# gain_mute.net
KiCad netlist of a schematic drawn in EAGLE
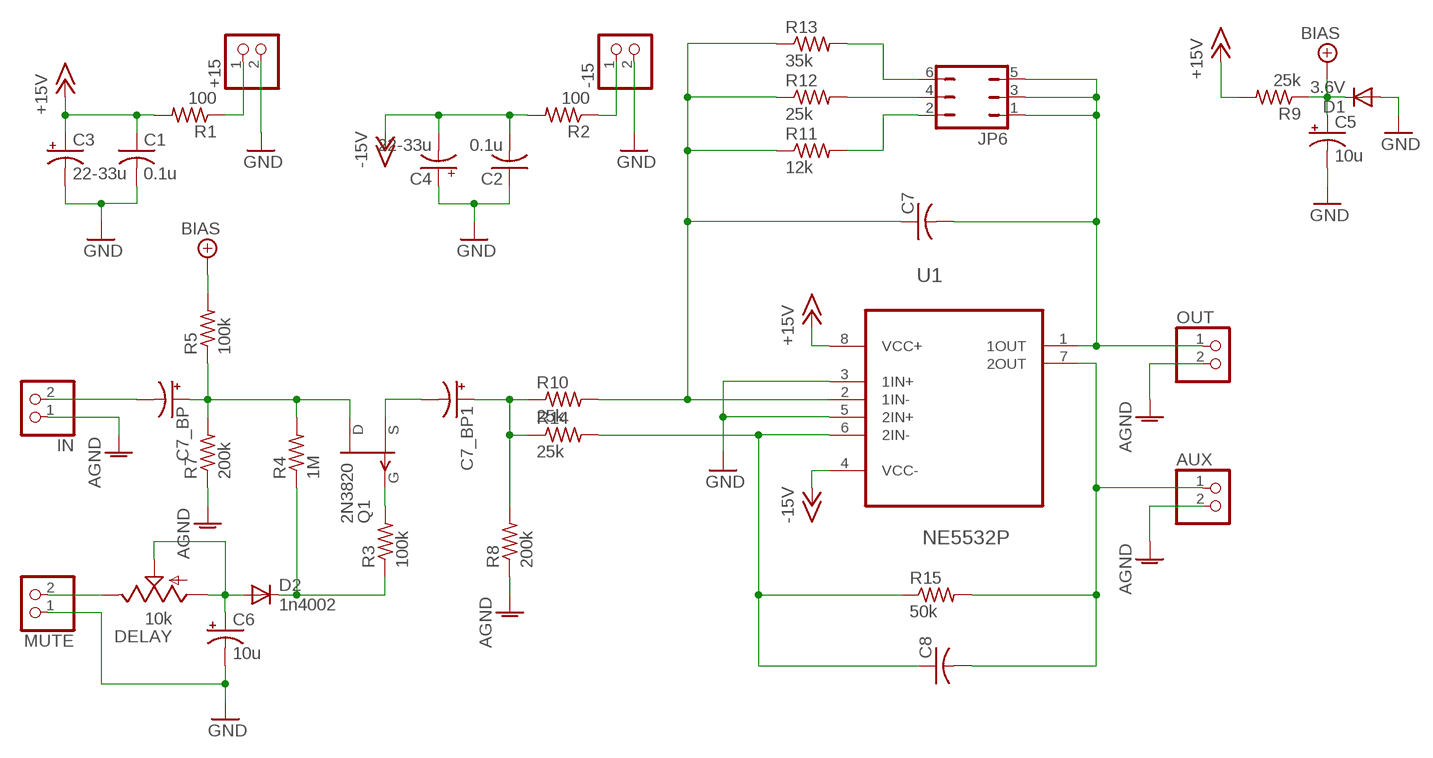
[diagram p0: schematic, sheet 1]

(export (version "E")
  (design (tool "Eeschema 10.0.6"))
  (components
    (comp (ref "+15")
      (value "PINHD-1X2")
      (footprint "eagle-import:1X02")
      (libsource (lib "eagle-import") (part "PINHD-1X2"))
    )
    (comp (ref "-15")
      (value "PINHD-1X2")
      (footprint "eagle-import:1X02")
      (libsource (lib "eagle-import") (part "PINHD-1X2"))
    )
    (comp (ref "AUX")
      (value "PINHD-1X2")
      (footprint "eagle-import:1X02")
      (libsource (lib "eagle-import") (part "PINHD-1X2"))
    )
    (comp (ref "C1")
      (value "0.1u")
      (footprint "eagle-import:C1206")
      (libsource (lib "eagle-import") (part "C-USC1206"))
    )
    (comp (ref "C2")
      (value "0.1u")
      (footprint "eagle-import:C1206")
      (libsource (lib "eagle-import") (part "C-USC1206"))
    )
    (comp (ref "C3")
      (value "22-33u")
      (footprint "eagle-import:E2-5")
      (libsource (lib "eagle-import") (part "CPOL-USE2-5"))
    )
    (comp (ref "C4")
      (value "22-33u")
      (footprint "eagle-import:E2-5")
      (libsource (lib "eagle-import") (part "CPOL-USE2-5"))
    )
    (comp (ref "C5")
      (value "10u")
      (footprint "eagle-import:E2-5")
      (libsource (lib "eagle-import") (part "CPOL-USE2-5"))
    )
    (comp (ref "C6")
      (value "10u")
      (footprint "eagle-import:E2-5")
      (libsource (lib "eagle-import") (part "CPOL-USE2-5"))
    )
    (comp (ref "C7")
      (value "C-US050-024X044")
      (footprint "eagle-import:C050-024X044")
      (libsource (lib "eagle-import") (part "C-US050-024X044"))
    )
    (comp (ref "C7_BP")
      (value "CPOL-USE2.5-7")
      (footprint "eagle-import:E2,5-7")
      (libsource (lib "eagle-import") (part "CPOL-USE2.5-7"))
    )
    (comp (ref "C7_BP1")
      (value "CPOL-USE2.5-7")
      (footprint "eagle-import:E2,5-7")
      (libsource (lib "eagle-import") (part "CPOL-USE2.5-7"))
    )
    (comp (ref "C8")
      (value "C-US050-024X044")
      (footprint "eagle-import:C050-024X044")
      (libsource (lib "eagle-import") (part "C-US050-024X044"))
    )
    (comp (ref "D1")
      (value "3.6V")
      (footprint "eagle-import:SOD123")
      (libsource (lib "eagle-import") (part "DIODE-SOD123"))
    )
    (comp (ref "D2")
      (value "1n4002")
      (footprint "eagle-import:SOD123")
      (libsource (lib "eagle-import") (part "DIODE-SOD123"))
    )
    (comp (ref "DELAY")
      (value "10k")
      (footprint "eagle-import:3223J")
      (libsource (lib "eagle-import") (part "TRIM_US-3223J"))
    )
    (comp (ref "IN")
      (value "PINHD-1X2")
      (footprint "eagle-import:1X02")
      (libsource (lib "eagle-import") (part "PINHD-1X2"))
    )
    (comp (ref "JP6")
      (value "JP3Q")
      (footprint "eagle-import:JP3Q")
      (libsource (lib "eagle-import") (part "JP3Q"))
    )
    (comp (ref "MUTE")
      (value "PINHD-1X2")
      (footprint "eagle-import:1X02")
      (libsource (lib "eagle-import") (part "PINHD-1X2"))
    )
    (comp (ref "OUT")
      (value "PINHD-1X2")
      (footprint "eagle-import:1X02")
      (libsource (lib "eagle-import") (part "PINHD-1X2"))
    )
    (comp (ref "Q1")
      (value "2N3820")
      (footprint "eagle-import:TO92")
      (libsource (lib "eagle-import") (part "2N3820"))
    )
    (comp (ref "R1")
      (value "100")
      (footprint "eagle-import:0207_7")
      (libsource (lib "eagle-import") (part "R-US_0207/7"))
    )
    (comp (ref "R2")
      (value "100")
      (footprint "eagle-import:0207_7")
      (libsource (lib "eagle-import") (part "R-US_0207/7"))
    )
    (comp (ref "R3")
      (value "100k")
      (footprint "eagle-import:R1206")
      (libsource (lib "eagle-import") (part "R-US_R1206"))
    )
    (comp (ref "R4")
      (value "1M")
      (footprint "eagle-import:R1206")
      (libsource (lib "eagle-import") (part "R-US_R1206"))
    )
    (comp (ref "R5")
      (value "100k")
      (footprint "eagle-import:R1206")
      (libsource (lib "eagle-import") (part "R-US_R1206"))
    )
    (comp (ref "R7")
      (value "200k")
      (footprint "eagle-import:R1206")
      (libsource (lib "eagle-import") (part "R-US_R1206"))
    )
    (comp (ref "R8")
      (value "200k")
      (footprint "eagle-import:R1206")
      (libsource (lib "eagle-import") (part "R-US_R1206"))
    )
    (comp (ref "R9")
      (value "25k")
      (footprint "eagle-import:R1206")
      (libsource (lib "eagle-import") (part "R-US_R1206"))
    )
    (comp (ref "R10")
      (value "25k")
      (footprint "eagle-import:0207_7")
      (libsource (lib "eagle-import") (part "R-US_0207/7"))
    )
    (comp (ref "R11")
      (value "12k")
      (footprint "eagle-import:0207_7")
      (libsource (lib "eagle-import") (part "R-US_0207/7"))
    )
    (comp (ref "R12")
      (value "25k")
      (footprint "eagle-import:0207_7")
      (libsource (lib "eagle-import") (part "R-US_0207/7"))
    )
    (comp (ref "R13")
      (value "35k")
      (footprint "eagle-import:0207_7")
      (libsource (lib "eagle-import") (part "R-US_0207/7"))
    )
    (comp (ref "R14")
      (value "25k")
      (footprint "eagle-import:0207_7")
      (libsource (lib "eagle-import") (part "R-US_0207/7"))
    )
    (comp (ref "R15")
      (value "50k")
      (footprint "eagle-import:0207_7")
      (libsource (lib "eagle-import") (part "R-US_0207/7"))
    )
    (comp (ref "U1")
      (value "NE5532P")
      (footprint "eagle-import:DIP254P762X508-8")
      (libsource (lib "eagle-import") (part "NE5532P"))
    )
  )
  (nets
    (net (code "1") (name "+15V") (class "Default")
      (node (ref "C1") (pin "1") (pinfunction "1_1") (pintype "passive"))
      (node (ref "C3") (pin "+") (pinfunction "+_+") (pintype "passive"))
      (node (ref "R1") (pin "2") (pinfunction "2_2") (pintype "passive"))
      (node (ref "R9") (pin "2") (pinfunction "2_2") (pintype "passive"))
      (node (ref "U1") (pin "8") (pinfunction "VCC+_8") (pintype "power_in"))
    )
    (net (code "2") (name "-15V") (class "Default")
      (node (ref "C2") (pin "2") (pinfunction "2_2") (pintype "passive"))
      (node (ref "C4") (pin "-") (pinfunction "-_-") (pintype "passive"))
      (node (ref "R2") (pin "2") (pinfunction "2_2") (pintype "passive"))
      (node (ref "U1") (pin "4") (pinfunction "VCC-_4") (pintype "power_in"))
    )
    (net (code "3") (name "AGND") (class "Default")
      (node (ref "AUX") (pin "2") (pinfunction "2_2") (pintype "passive"))
      (node (ref "IN") (pin "1") (pinfunction "1_1") (pintype "passive"))
      (node (ref "OUT") (pin "2") (pinfunction "2_2") (pintype "passive"))
      (node (ref "R7") (pin "1") (pinfunction "1_1") (pintype "passive"))
      (node (ref "R8") (pin "1") (pinfunction "1_1") (pintype "passive"))
    )
    (net (code "4") (name "BIAS") (class "Default")
      (node (ref "C5") (pin "+") (pinfunction "+_+") (pintype "passive"))
      (node (ref "D1") (pin "C") (pinfunction "C_C") (pintype "passive"))
      (node (ref "R5") (pin "2") (pinfunction "2_2") (pintype "passive"))
      (node (ref "R9") (pin "1") (pinfunction "1_1") (pintype "passive"))
    )
    (net (code "5") (name "GND") (class "Default")
      (node (ref "+15") (pin "2") (pinfunction "2_2") (pintype "passive"))
      (node (ref "-15") (pin "2") (pinfunction "2_2") (pintype "passive"))
      (node (ref "C1") (pin "2") (pinfunction "2_2") (pintype "passive"))
      (node (ref "C2") (pin "1") (pinfunction "1_1") (pintype "passive"))
      (node (ref "C3") (pin "-") (pinfunction "-_-") (pintype "passive"))
      (node (ref "C4") (pin "+") (pinfunction "+_+") (pintype "passive"))
      (node (ref "C5") (pin "-") (pinfunction "-_-") (pintype "passive"))
      (node (ref "C6") (pin "-") (pinfunction "-_-") (pintype "passive"))
      (node (ref "D1") (pin "A") (pinfunction "A_A") (pintype "passive"))
      (node (ref "MUTE") (pin "1") (pinfunction "1_1") (pintype "passive"))
      (node (ref "U1") (pin "3") (pinfunction "1IN+_3") (pintype "input"))
      (node (ref "U1") (pin "5") (pinfunction "2IN+_5") (pintype "input"))
    )
    (net (code "6") (name "Net-(+15-Pad1)") (class "Default")
      (node (ref "+15") (pin "1") (pinfunction "1_1") (pintype "passive"))
      (node (ref "R1") (pin "1") (pinfunction "1_1") (pintype "passive"))
    )
    (net (code "7") (name "Net-(-15-Pad1)") (class "Default")
      (node (ref "-15") (pin "1") (pinfunction "1_1") (pintype "passive"))
      (node (ref "R2") (pin "1") (pinfunction "1_1") (pintype "passive"))
    )
    (net (code "8") (name "Net-(C7_BP-Pad-)") (class "Default")
      (node (ref "C7_BP") (pin "-") (pinfunction "-_-") (pintype "passive"))
      (node (ref "IN") (pin "2") (pinfunction "2_2") (pintype "passive"))
    )
    (net (code "9") (name "Net-(C7_BP1-Pad+)") (class "Default")
      (node (ref "C7_BP1") (pin "+") (pinfunction "+_+") (pintype "passive"))
      (node (ref "R10") (pin "1") (pinfunction "1_1") (pintype "passive"))
      (node (ref "R14") (pin "1") (pinfunction "1_1") (pintype "passive"))
      (node (ref "R8") (pin "2") (pinfunction "2_2") (pintype "passive"))
    )
    (net (code "10") (name "Net-(D2-PadC)") (class "Default")
      (node (ref "D2") (pin "C") (pinfunction "C_C") (pintype "passive"))
      (node (ref "R3") (pin "1") (pinfunction "1_1") (pintype "passive"))
      (node (ref "R4") (pin "1") (pinfunction "1_1") (pintype "passive"))
    )
    (net (code "11") (name "Net-(DELAY-A)") (class "Default")
      (node (ref "C6") (pin "+") (pinfunction "+_+") (pintype "passive"))
      (node (ref "D2") (pin "A") (pinfunction "A_A") (pintype "passive"))
      (node (ref "DELAY") (pin "1") (pinfunction "A_1") (pintype "passive"))
      (node (ref "DELAY") (pin "2") (pinfunction "S_2") (pintype "passive"))
    )
    (net (code "12") (name "Net-(DELAY-E)") (class "Default")
      (node (ref "DELAY") (pin "3") (pinfunction "E_3") (pintype "passive"))
      (node (ref "MUTE") (pin "2") (pinfunction "2_2") (pintype "passive"))
    )
    (net (code "13") (name "Net-(JP6-Pad2)") (class "Default")
      (node (ref "JP6") (pin "2") (pinfunction "2_2") (pintype "passive"))
      (node (ref "R11") (pin "2") (pinfunction "2_2") (pintype "passive"))
    )
    (net (code "14") (name "Net-(JP6-Pad4)") (class "Default")
      (node (ref "JP6") (pin "4") (pinfunction "4_4") (pintype "passive"))
      (node (ref "R12") (pin "2") (pinfunction "2_2") (pintype "passive"))
    )
    (net (code "15") (name "Net-(JP6-Pad6)") (class "Default")
      (node (ref "JP6") (pin "6") (pinfunction "6_6") (pintype "passive"))
      (node (ref "R13") (pin "2") (pinfunction "2_2") (pintype "passive"))
    )
    (net (code "16") (name "Net-(Q1-D)") (class "Default")
      (node (ref "C7_BP") (pin "+") (pinfunction "+_+") (pintype "passive"))
      (node (ref "Q1") (pin "3") (pinfunction "D_3") (pintype "passive"))
      (node (ref "R4") (pin "2") (pinfunction "2_2") (pintype "passive"))
      (node (ref "R5") (pin "1") (pinfunction "1_1") (pintype "passive"))
      (node (ref "R7") (pin "2") (pinfunction "2_2") (pintype "passive"))
    )
    (net (code "17") (name "Net-(Q1-G)") (class "Default")
      (node (ref "Q1") (pin "2") (pinfunction "G_2") (pintype "passive"))
      (node (ref "R3") (pin "2") (pinfunction "2_2") (pintype "passive"))
    )
    (net (code "18") (name "Net-(Q1-S)") (class "Default")
      (node (ref "C7_BP1") (pin "-") (pinfunction "-_-") (pintype "passive"))
      (node (ref "Q1") (pin "1") (pinfunction "S_1") (pintype "passive"))
    )
    (net (code "19") (name "Net-(U1-1IN-)") (class "Default")
      (node (ref "C7") (pin "1") (pinfunction "1_1") (pintype "passive"))
      (node (ref "R10") (pin "2") (pinfunction "2_2") (pintype "passive"))
      (node (ref "R11") (pin "1") (pinfunction "1_1") (pintype "passive"))
      (node (ref "R12") (pin "1") (pinfunction "1_1") (pintype "passive"))
      (node (ref "R13") (pin "1") (pinfunction "1_1") (pintype "passive"))
      (node (ref "U1") (pin "2") (pinfunction "1IN-_2") (pintype "input"))
    )
    (net (code "20") (name "Net-(U1-1OUT)") (class "Default")
      (node (ref "C7") (pin "2") (pinfunction "2_2") (pintype "passive"))
      (node (ref "JP6") (pin "1") (pinfunction "1_1") (pintype "passive"))
      (node (ref "JP6") (pin "3") (pinfunction "3_3") (pintype "passive"))
      (node (ref "JP6") (pin "5") (pinfunction "5_5") (pintype "passive"))
      (node (ref "OUT") (pin "1") (pinfunction "1_1") (pintype "passive"))
      (node (ref "U1") (pin "1") (pinfunction "1OUT_1") (pintype "output"))
    )
    (net (code "21") (name "Net-(U1-2IN-)") (class "Default")
      (node (ref "C8") (pin "1") (pinfunction "1_1") (pintype "passive"))
      (node (ref "R14") (pin "2") (pinfunction "2_2") (pintype "passive"))
      (node (ref "R15") (pin "1") (pinfunction "1_1") (pintype "passive"))
      (node (ref "U1") (pin "6") (pinfunction "2IN-_6") (pintype "input"))
    )
    (net (code "22") (name "Net-(U1-2OUT)") (class "Default")
      (node (ref "AUX") (pin "1") (pinfunction "1_1") (pintype "passive"))
      (node (ref "C8") (pin "2") (pinfunction "2_2") (pintype "passive"))
      (node (ref "R15") (pin "2") (pinfunction "2_2") (pintype "passive"))
      (node (ref "U1") (pin "7") (pinfunction "2OUT_7") (pintype "output"))
    )
  )
)
